# PanelPCB.net
KiCad netlist of a schematic drawn in EAGLE
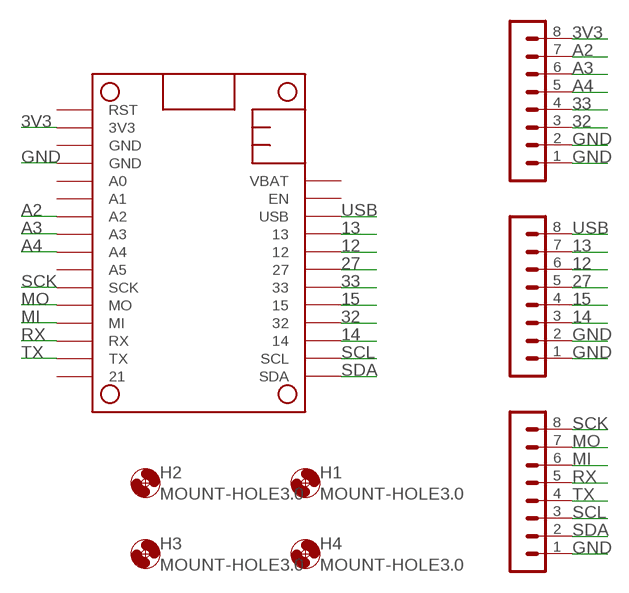
[diagram p0: schematic, sheet 1]

(export (version "E")
  (design (tool "Eeschema 10.0.6"))
  (components
    (comp (ref "H1")
      (value "MOUNT-HOLE3.0")
      (footprint "eagle-import:3,0")
      (libsource (lib "eagle-import") (part "MOUNT-HOLE3.0"))
    )
    (comp (ref "H2")
      (value "MOUNT-HOLE3.0")
      (footprint "eagle-import:3,0")
      (libsource (lib "eagle-import") (part "MOUNT-HOLE3.0"))
    )
    (comp (ref "H3")
      (value "MOUNT-HOLE3.0")
      (footprint "eagle-import:3,0")
      (libsource (lib "eagle-import") (part "MOUNT-HOLE3.0"))
    )
    (comp (ref "H4")
      (value "MOUNT-HOLE3.0")
      (footprint "eagle-import:3,0")
      (libsource (lib "eagle-import") (part "MOUNT-HOLE3.0"))
    )
    (comp (ref "M1")
      (value "RARNDT-MISCELANEOUS_FEATHERBOARD_ESP32FETHERWING_DIM_ESP32")
      (footprint "eagle-import:RARNDT-MISCELANEOUS_FEATHERBOARD_ESP32")
      (libsource (lib "eagle-import") (part "RARNDT-MISCELANEOUS_FEATHERBOARD_ESP32FETHERWING_DIM_ESP32"))
    )
    (comp (ref "SV1")
      (value "MA08-1")
      (footprint "eagle-import:MA08-1")
      (libsource (lib "eagle-import") (part "MA08-1"))
    )
    (comp (ref "SV2")
      (value "MA08-1")
      (footprint "eagle-import:MA08-1")
      (libsource (lib "eagle-import") (part "MA08-1"))
    )
    (comp (ref "SV3")
      (value "MA08-1")
      (footprint "eagle-import:MA08-1")
      (libsource (lib "eagle-import") (part "MA08-1"))
    )
  )
  (nets
    (net (code "1") (name "/3V3") (class "Default")
      (node (ref "M1") (pin "2") (pinfunction "3V3_2") (pintype "power_in"))
      (node (ref "SV1") (pin "8") (pinfunction "8_8") (pintype "passive"))
    )
    (net (code "2") (name "/12") (class "Default")
      (node (ref "M1") (pin "24") (pinfunction "12_24") (pintype "bidirectional"))
      (node (ref "SV2") (pin "6") (pinfunction "6_6") (pintype "passive"))
    )
    (net (code "3") (name "/13") (class "Default")
      (node (ref "M1") (pin "25") (pinfunction "13_25") (pintype "bidirectional"))
      (node (ref "SV2") (pin "7") (pinfunction "7_7") (pintype "passive"))
    )
    (net (code "4") (name "/14") (class "Default")
      (node (ref "M1") (pin "19") (pinfunction "14_19") (pintype "bidirectional"))
      (node (ref "SV2") (pin "3") (pinfunction "3_3") (pintype "passive"))
    )
    (net (code "5") (name "/15") (class "Default")
      (node (ref "M1") (pin "21") (pinfunction "15_21") (pintype "bidirectional"))
      (node (ref "SV2") (pin "4") (pinfunction "4_4") (pintype "passive"))
    )
    (net (code "6") (name "/27") (class "Default")
      (node (ref "M1") (pin "23") (pinfunction "27_23") (pintype "bidirectional"))
      (node (ref "SV2") (pin "5") (pinfunction "5_5") (pintype "passive"))
    )
    (net (code "7") (name "/32") (class "Default")
      (node (ref "M1") (pin "20") (pinfunction "32_20") (pintype "bidirectional"))
      (node (ref "SV1") (pin "3") (pinfunction "3_3") (pintype "passive"))
    )
    (net (code "8") (name "/33") (class "Default")
      (node (ref "M1") (pin "22") (pinfunction "33_22") (pintype "bidirectional"))
      (node (ref "SV1") (pin "4") (pinfunction "4_4") (pintype "passive"))
    )
    (net (code "9") (name "/A2") (class "Default")
      (node (ref "M1") (pin "7") (pinfunction "A2_7") (pintype "bidirectional"))
      (node (ref "SV1") (pin "7") (pinfunction "7_7") (pintype "passive"))
    )
    (net (code "10") (name "/A3") (class "Default")
      (node (ref "M1") (pin "8") (pinfunction "A3_8") (pintype "bidirectional"))
      (node (ref "SV1") (pin "6") (pinfunction "6_6") (pintype "passive"))
    )
    (net (code "11") (name "/A4") (class "Default")
      (node (ref "M1") (pin "9") (pinfunction "A4_9") (pintype "bidirectional"))
      (node (ref "SV1") (pin "5") (pinfunction "5_5") (pintype "passive"))
    )
    (net (code "12") (name "/GND") (class "Default")
      (node (ref "M1") (pin "4") (pinfunction "GND_4") (pintype "power_in"))
      (node (ref "SV1") (pin "1") (pinfunction "1_1") (pintype "passive"))
      (node (ref "SV1") (pin "2") (pinfunction "2_2") (pintype "passive"))
      (node (ref "SV2") (pin "1") (pinfunction "1_1") (pintype "passive"))
      (node (ref "SV2") (pin "2") (pinfunction "2_2") (pintype "passive"))
      (node (ref "SV3") (pin "1") (pinfunction "1_1") (pintype "passive"))
    )
    (net (code "13") (name "/MI") (class "Default")
      (node (ref "M1") (pin "13") (pinfunction "MI_13") (pintype "bidirectional"))
      (node (ref "SV3") (pin "6") (pinfunction "6_6") (pintype "passive"))
    )
    (net (code "14") (name "/MO") (class "Default")
      (node (ref "M1") (pin "12") (pinfunction "MO_12") (pintype "bidirectional"))
      (node (ref "SV3") (pin "7") (pinfunction "7_7") (pintype "passive"))
    )
    (net (code "15") (name "/RX") (class "Default")
      (node (ref "M1") (pin "14") (pinfunction "RX_14") (pintype "bidirectional"))
      (node (ref "SV3") (pin "5") (pinfunction "5_5") (pintype "passive"))
    )
    (net (code "16") (name "/SCK") (class "Default")
      (node (ref "M1") (pin "11") (pinfunction "SCK_11") (pintype "bidirectional"))
      (node (ref "SV3") (pin "8") (pinfunction "8_8") (pintype "passive"))
    )
    (net (code "17") (name "/SCL") (class "Default")
      (node (ref "M1") (pin "18") (pinfunction "SCL_18") (pintype "bidirectional"))
      (node (ref "SV3") (pin "3") (pinfunction "3_3") (pintype "passive"))
    )
    (net (code "18") (name "/SDA") (class "Default")
      (node (ref "M1") (pin "17") (pinfunction "SDA_17") (pintype "bidirectional"))
      (node (ref "SV3") (pin "2") (pinfunction "2_2") (pintype "passive"))
    )
    (net (code "19") (name "/TX") (class "Default")
      (node (ref "M1") (pin "15") (pinfunction "TX_15") (pintype "bidirectional"))
      (node (ref "SV3") (pin "4") (pinfunction "4_4") (pintype "passive"))
    )
    (net (code "20") (name "/USB") (class "Default")
      (node (ref "M1") (pin "26") (pinfunction "USB_26") (pintype "power_in"))
      (node (ref "SV2") (pin "8") (pinfunction "8_8") (pintype "passive"))
    )
    (net (code "21") (name "/VBAT") (class "Default")
      (node (ref "M1") (pin "28") (pinfunction "VBAT_28") (pintype "power_in"))
    )
    (net (code "22") (name "unconnected-(M1-21-Pad16)") (class "Default")
      (node (ref "M1") (pin "16") (pinfunction "21_16") (pintype "passive"))
    )
    (net (code "23") (name "unconnected-(M1-A0-Pad5)") (class "Default")
      (node (ref "M1") (pin "5") (pinfunction "A0_5") (pintype "bidirectional"))
    )
    (net (code "24") (name "unconnected-(M1-A1-Pad6)") (class "Default")
      (node (ref "M1") (pin "6") (pinfunction "A1_6") (pintype "bidirectional"))
    )
    (net (code "25") (name "unconnected-(M1-A5-Pad10)") (class "Default")
      (node (ref "M1") (pin "10") (pinfunction "A5_10") (pintype "bidirectional"))
    )
    (net (code "26") (name "unconnected-(M1-EN-Pad27)") (class "Default")
      (node (ref "M1") (pin "27") (pinfunction "EN_27") (pintype "passive"))
    )
    (net (code "27") (name "unconnected-(M1-GND-Pad3)") (class "Default")
      (node (ref "M1") (pin "3") (pinfunction "GND_3") (pintype "passive"))
    )
    (net (code "28") (name "unconnected-(M1-RST-Pad1)") (class "Default")
      (node (ref "M1") (pin "1") (pinfunction "RST_1") (pintype "input"))
    )
  )
)
